# Sensors.net
KiCad netlist of a schematic drawn in Altium Designer
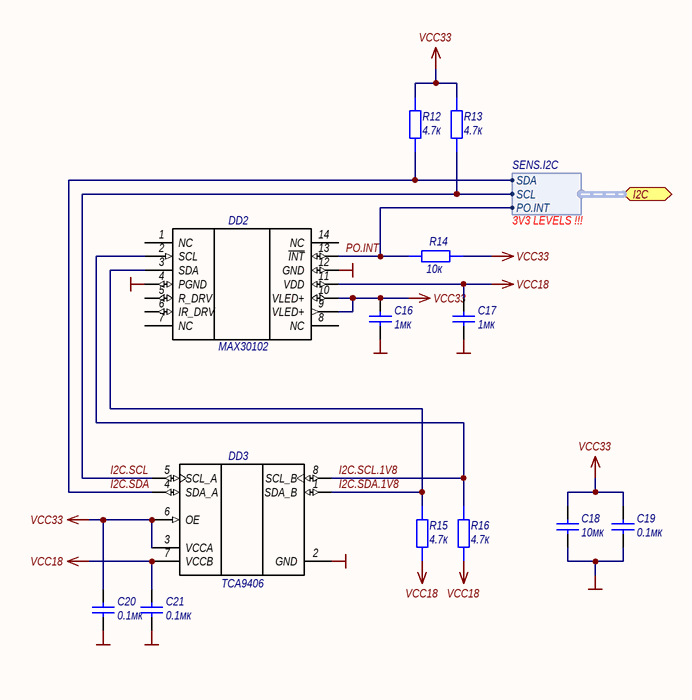
[diagram p0: Sensors.SchDoc]

(export (version "E")
  (design (tool "Eeschema 10.0.6"))
  (components
    (comp (ref "C16")
      (value "1мк")
      (footprint "CAPC1005L")
      (description "Samsung MLCC Capacitor")
      (fields
        (field (name "MANUFACTURER") "Samsung")
        (field (name "MANUFACTURERPARTNUMBER") "CL05A105KQ5NNN")
        (field (name "PUBLISHER") "Komiss Labs.")
      )
      (libsource (lib "Samsung_MLCC_Capacitors") (part "CL05"))
    )
    (comp (ref "C17")
      (value "1мк")
      (footprint "CAPC1005L")
      (description "Samsung MLCC Capacitor")
      (fields
        (field (name "MANUFACTURER") "Samsung")
        (field (name "MANUFACTURERPARTNUMBER") "CL05A105KQ5NNN")
        (field (name "PUBLISHER") "Komiss Labs.")
      )
      (libsource (lib "Samsung_MLCC_Capacitors") (part "CL05"))
    )
    (comp (ref "C18")
      (value "10мк")
      (footprint "CAPC1005L")
      (description "Samsung MLCC Capacitor")
      (fields
        (field (name "MANUFACTURER") "Samsung")
        (field (name "MANUFACTURERPARTNUMBER") "CL05A106MQ5NUN")
        (field (name "PUBLISHER") "Komiss Labs.")
      )
      (libsource (lib "Samsung_MLCC_Capacitors") (part "CL05"))
    )
    (comp (ref "C19")
      (value "0.1мк")
      (footprint "CAPC1005L")
      (description "Samsung MLCC Capacitor")
      (fields
        (field (name "MANUFACTURER") "Samsung")
        (field (name "MANUFACTURERPARTNUMBER") "CL05A104KP5NNN")
        (field (name "PUBLISHER") "Komiss Labs.")
      )
      (libsource (lib "Samsung_MLCC_Capacitors") (part "CL05"))
    )
    (comp (ref "C20")
      (value "0.1мк")
      (footprint "CAPC1005L")
      (description "Samsung MLCC Capacitor")
      (fields
        (field (name "MANUFACTURER") "Samsung")
        (field (name "MANUFACTURERPARTNUMBER") "CL05A104KP5NNN")
        (field (name "PUBLISHER") "Komiss Labs.")
      )
      (libsource (lib "Samsung_MLCC_Capacitors") (part "CL05"))
    )
    (comp (ref "C21")
      (value "0.1мк")
      (footprint "CAPC1005L")
      (description "Samsung MLCC Capacitor")
      (fields
        (field (name "MANUFACTURER") "Samsung")
        (field (name "MANUFACTURERPARTNUMBER") "CL05A104KP5NNN")
        (field (name "PUBLISHER") "Komiss Labs.")
      )
      (libsource (lib "Samsung_MLCC_Capacitors") (part "CL05"))
    )
    (comp (ref "DD2")
      (value "MAX30102")
      (footprint "MAX30102")
      (description "High-Sensitivity Pulse Oximeter and  Heart-Rate Sensor for Wearable Health")
      (fields (field (name "MANUFACTURER") "MAXIM Integrated"))
      (libsource (lib "MySchLib") (part "MAX30102"))
    )
    (comp (ref "DD3")
      (value "TCA9406")
      (footprint "Interface_I2C:DCU8_L")
      (fields (field (name "MANUFACTURER") "Texas Instruments"))
      (libsource (lib "MySchLib") (part "TCA9406"))
    )
    (comp (ref "R12")
      (value "4.7к")
      (footprint "RESC1005L")
      (description "General Thick Film Chip Resistor")
      (fields
        (field (name "TOLERANCE") "±5%")
        (field (name "MANUFACTURER") "Samsung")
        (field (name "PUBLISHER") "Komiss Labs.")
      )
      (libsource (lib "Samsung_Chip_Resistors") (part "RC1005"))
    )
    (comp (ref "R13")
      (value "4.7к")
      (footprint "RESC1005L")
      (description "General Thick Film Chip Resistor")
      (fields
        (field (name "TOLERANCE") "±5%")
        (field (name "MANUFACTURER") "Samsung")
        (field (name "PUBLISHER") "Komiss Labs.")
      )
      (libsource (lib "Samsung_Chip_Resistors") (part "RC1005"))
    )
    (comp (ref "R14")
      (value "10к")
      (footprint "RESC1005L")
      (description "General Thick Film Chip Resistor")
      (fields
        (field (name "TOLERANCE") "±5%")
        (field (name "MANUFACTURER") "Samsung")
        (field (name "PUBLISHER") "Komiss Labs.")
      )
      (libsource (lib "Samsung_Chip_Resistors") (part "RC1005"))
    )
    (comp (ref "R15")
      (value "4.7к")
      (footprint "RESC1005L")
      (description "General Thick Film Chip Resistor")
      (fields
        (field (name "TOLERANCE") "±5%")
        (field (name "MANUFACTURER") "Samsung")
        (field (name "PUBLISHER") "Komiss Labs.")
      )
      (libsource (lib "Samsung_Chip_Resistors") (part "RC1005"))
    )
    (comp (ref "R16")
      (value "4.7к")
      (footprint "RESC1005L")
      (description "General Thick Film Chip Resistor")
      (fields
        (field (name "TOLERANCE") "±5%")
        (field (name "MANUFACTURER") "Samsung")
        (field (name "PUBLISHER") "Komiss Labs.")
      )
      (libsource (lib "Samsung_Chip_Resistors") (part "RC1005"))
    )
  )
  (nets
    (net (code "2") (name "/I2C.SCL") (class "Default")
      (node (ref "DD3") (pin "5") (pinfunction "SCL_A_5") (pintype "bidirectional"))
      (node (ref "R13") (pin "1") (pinfunction "1_1") (pintype "passive"))
    )
    (net (code "3") (name "/I2C.SCL.1V8") (class "Default")
      (node (ref "DD2") (pin "2") (pinfunction "SCL_2") (pintype "input"))
      (node (ref "DD3") (pin "8") (pinfunction "SCL_B_8") (pintype "bidirectional"))
      (node (ref "R16") (pin "2") (pinfunction "2_2") (pintype "passive"))
    )
    (net (code "4") (name "/I2C.SDA") (class "Default")
      (node (ref "DD3") (pin "4") (pinfunction "SDA_A_4") (pintype "bidirectional"))
      (node (ref "R12") (pin "1") (pinfunction "1_1") (pintype "passive"))
    )
    (net (code "5") (name "/I2C.SDA.1V8") (class "Default")
      (node (ref "DD2") (pin "3") (pinfunction "SDA_3") (pintype "passive"))
      (node (ref "DD3") (pin "1") (pinfunction "SDA_B_1") (pintype "bidirectional"))
      (node (ref "R15") (pin "2") (pinfunction "2_2") (pintype "passive"))
    )
    (net (code "6") (name "/PO.INT") (class "Default")
      (node (ref "DD2") (pin "13") (pinfunction "~{INT}_13") (pintype "bidirectional"))
      (node (ref "R14") (pin "2") (pinfunction "2_2") (pintype "passive"))
    )
    (net (code "8") (name "GND") (class "Default")
      (node (ref "C16") (pin "1") (pinfunction "1_1") (pintype "passive"))
      (node (ref "C17") (pin "1") (pinfunction "1_1") (pintype "passive"))
      (node (ref "C18") (pin "1") (pinfunction "1_1") (pintype "passive"))
      (node (ref "C19") (pin "1") (pinfunction "1_1") (pintype "passive"))
      (node (ref "C20") (pin "1") (pinfunction "1_1") (pintype "passive"))
      (node (ref "C21") (pin "1") (pinfunction "1_1") (pintype "passive"))
      (node (ref "DD2") (pin "12") (pinfunction "GND_12") (pintype "bidirectional"))
      (node (ref "DD2") (pin "4") (pinfunction "PGND_4") (pintype "bidirectional"))
      (node (ref "DD3") (pin "2") (pinfunction "GND_2") (pintype "power_in"))
    )
    (net (code "9") (name "VCC18") (class "Default")
      (node (ref "C17") (pin "2") (pinfunction "2_2") (pintype "passive"))
      (node (ref "C21") (pin "2") (pinfunction "2_2") (pintype "passive"))
      (node (ref "DD2") (pin "11") (pinfunction "VDD_11") (pintype "bidirectional"))
      (node (ref "DD3") (pin "7") (pinfunction "VCCB_7") (pintype "power_in"))
      (node (ref "R15") (pin "1") (pinfunction "1_1") (pintype "passive"))
      (node (ref "R16") (pin "1") (pinfunction "1_1") (pintype "passive"))
    )
    (net (code "10") (name "VCC33") (class "Default")
      (node (ref "C16") (pin "2") (pinfunction "2_2") (pintype "passive"))
      (node (ref "C18") (pin "2") (pinfunction "2_2") (pintype "passive"))
      (node (ref "C19") (pin "2") (pinfunction "2_2") (pintype "passive"))
      (node (ref "C20") (pin "2") (pinfunction "2_2") (pintype "passive"))
      (node (ref "DD2") (pin "10") (pinfunction "VLED+_10") (pintype "bidirectional"))
      (node (ref "DD2") (pin "9") (pinfunction "VLED+_9") (pintype "output"))
      (node (ref "DD3") (pin "3") (pinfunction "VCCA_3") (pintype "power_in"))
      (node (ref "DD3") (pin "6") (pinfunction "OE_6") (pintype "input"))
      (node (ref "R12") (pin "2") (pinfunction "2_2") (pintype "passive"))
      (node (ref "R13") (pin "2") (pinfunction "2_2") (pintype "passive"))
      (node (ref "R14") (pin "1") (pinfunction "1_1") (pintype "passive"))
    )
    (net (code "11") (name "unconnected-(DD2-IR_DRV-Pad6)") (class "Default")
      (node (ref "DD2") (pin "6") (pinfunction "IR_DRV_6") (pintype "bidirectional"))
    )
    (net (code "12") (name "unconnected-(DD2-NC-Pad1)") (class "Default")
      (node (ref "DD2") (pin "1") (pinfunction "NC_1") (pintype "passive"))
    )
    (net (code "13") (name "unconnected-(DD2-NC-Pad7)") (class "Default")
      (node (ref "DD2") (pin "7") (pinfunction "NC_7") (pintype "passive"))
    )
    (net (code "14") (name "unconnected-(DD2-NC-Pad8)") (class "Default")
      (node (ref "DD2") (pin "8") (pinfunction "NC_8") (pintype "passive"))
    )
    (net (code "15") (name "unconnected-(DD2-NC-Pad14)") (class "Default")
      (node (ref "DD2") (pin "14") (pinfunction "NC_14") (pintype "passive"))
    )
    (net (code "16") (name "unconnected-(DD2-R_DRV-Pad5)") (class "Default")
      (node (ref "DD2") (pin "5") (pinfunction "R_DRV_5") (pintype "bidirectional"))
    )
  )
)
